# hdmi.net
KiCad netlist of a schematic drawn in EAGLE
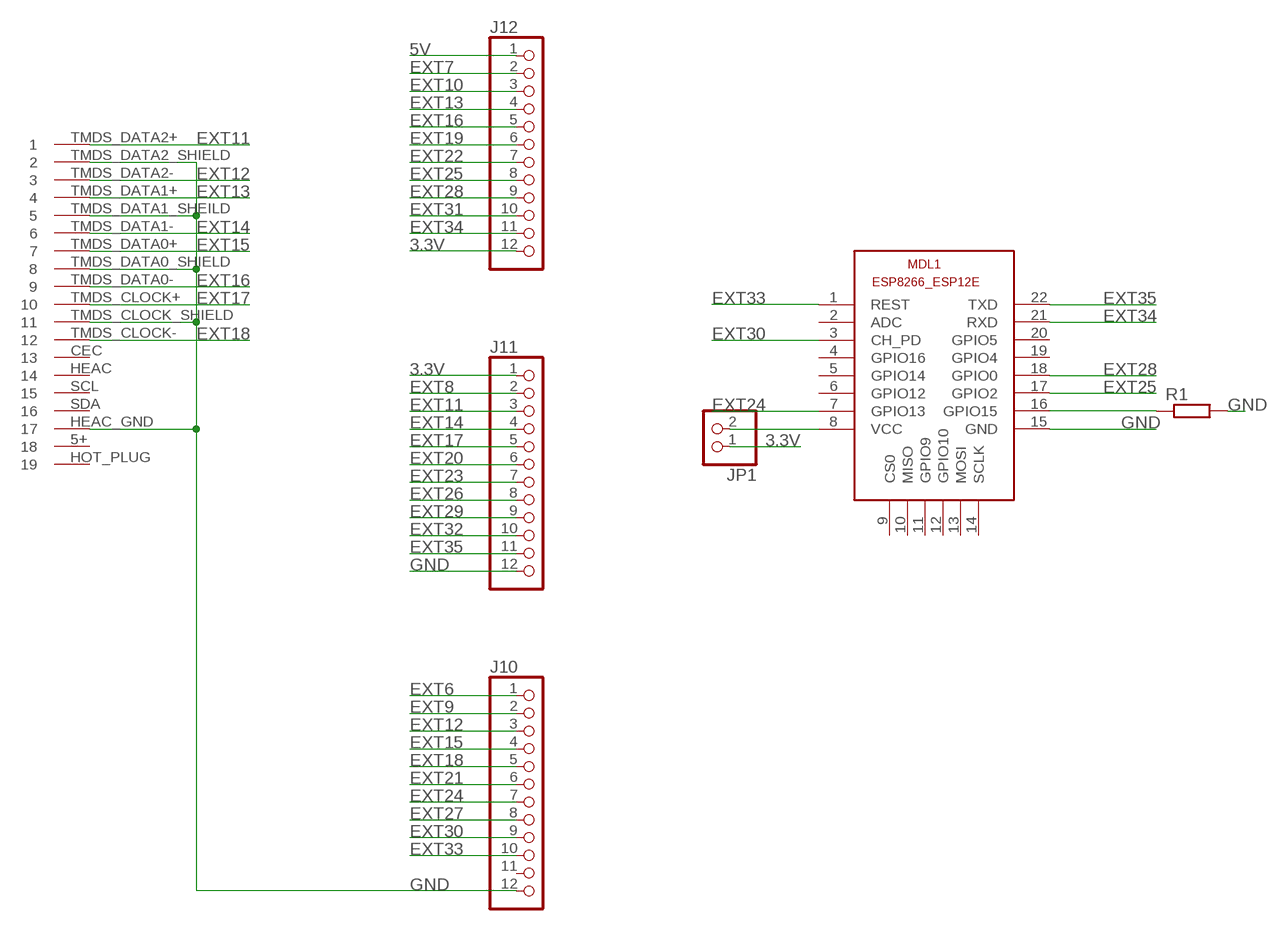
[diagram p0: schematic, sheet 1]

(export (version "E")
  (design (tool "Eeschema 10.0.6"))
  (components
    (comp (ref "J10")
      (value "PINHD-1X12")
      (footprint "eagle-import:1X12")
      (libsource (lib "eagle-import") (part "PINHD-1X12"))
    )
    (comp (ref "J11")
      (value "PINHD-1X12")
      (footprint "eagle-import:1X12")
      (libsource (lib "eagle-import") (part "PINHD-1X12"))
    )
    (comp (ref "J12")
      (value "PINHD-1X12")
      (footprint "eagle-import:1X12")
      (libsource (lib "eagle-import") (part "PINHD-1X12"))
    )
    (comp (ref "JP1")
      (value "PINHD-1X2/90")
      (footprint "eagle-import:1X02_90")
      (libsource (lib "eagle-import") (part "PINHD-1X2/90"))
    )
    (comp (ref "MDL1")
      (value "ESP8266-12EESP8266-ESP12E")
      (footprint "eagle-import:ESP8266-ESP12E")
      (libsource (lib "eagle-import") (part "ESP8266-12EESP8266-ESP12E"))
    )
    (comp (ref "R1")
      (value "R-EU_M0805")
      (footprint "eagle-import:M0805")
      (libsource (lib "eagle-import") (part "R-EU_M0805"))
    )
    (comp (ref "U$2")
      (value "HDMI")
      (footprint "eagle-import:DS1115")
      (libsource (lib "eagle-import") (part "HDMI"))
    )
  )
  (nets
    (net (code "1") (name "/3.3V") (class "Default")
      (node (ref "J11") (pin "1") (pinfunction "1_1") (pintype "passive"))
      (node (ref "J12") (pin "12") (pinfunction "12_12") (pintype "passive"))
      (node (ref "JP1") (pin "1") (pinfunction "1_1") (pintype "passive"))
    )
    (net (code "2") (name "/5V") (class "Default")
      (node (ref "J12") (pin "1") (pinfunction "1_1") (pintype "passive"))
    )
    (net (code "3") (name "/EXT6") (class "Default")
      (node (ref "J10") (pin "1") (pinfunction "1_1") (pintype "passive"))
    )
    (net (code "4") (name "/EXT7") (class "Default")
      (node (ref "J12") (pin "2") (pinfunction "2_2") (pintype "passive"))
    )
    (net (code "5") (name "/EXT8") (class "Default")
      (node (ref "J11") (pin "2") (pinfunction "2_2") (pintype "passive"))
    )
    (net (code "6") (name "/EXT9") (class "Default")
      (node (ref "J10") (pin "2") (pinfunction "2_2") (pintype "passive"))
    )
    (net (code "7") (name "/EXT10") (class "Default")
      (node (ref "J12") (pin "3") (pinfunction "3_3") (pintype "passive"))
    )
    (net (code "8") (name "/EXT11") (class "Default")
      (node (ref "J11") (pin "3") (pinfunction "3_3") (pintype "passive"))
      (node (ref "U$2") (pin "TMDS_DATA2+") (pinfunction "1_TMDS_DATA2+") (pintype "bidirectional"))
    )
    (net (code "9") (name "/EXT12") (class "Default")
      (node (ref "J10") (pin "3") (pinfunction "3_3") (pintype "passive"))
      (node (ref "U$2") (pin "TMDS_DATA2-") (pinfunction "3_TMDS_DATA2-") (pintype "bidirectional"))
    )
    (net (code "10") (name "/EXT13") (class "Default")
      (node (ref "J12") (pin "4") (pinfunction "4_4") (pintype "passive"))
      (node (ref "U$2") (pin "TMDS_DATA1+") (pinfunction "4_TMDS_DATA1+") (pintype "bidirectional"))
    )
    (net (code "11") (name "/EXT14") (class "Default")
      (node (ref "J11") (pin "4") (pinfunction "4_4") (pintype "passive"))
      (node (ref "U$2") (pin "TMDS_DATA1-") (pinfunction "6_TMDS_DATA1-") (pintype "bidirectional"))
    )
    (net (code "12") (name "/EXT15") (class "Default")
      (node (ref "J10") (pin "4") (pinfunction "4_4") (pintype "passive"))
      (node (ref "U$2") (pin "TMDS_DATA0+") (pinfunction "7_TMDS_DATA0+") (pintype "bidirectional"))
    )
    (net (code "13") (name "/EXT16") (class "Default")
      (node (ref "J12") (pin "5") (pinfunction "5_5") (pintype "passive"))
      (node (ref "U$2") (pin "TMDS_DATA0-") (pinfunction "9_TMDS_DATA0-") (pintype "bidirectional"))
    )
    (net (code "14") (name "/EXT17") (class "Default")
      (node (ref "J11") (pin "5") (pinfunction "5_5") (pintype "passive"))
      (node (ref "U$2") (pin "TMDS_CLOCK+") (pinfunction "10_TMDS_CLOCK+") (pintype "bidirectional"))
    )
    (net (code "15") (name "/EXT18") (class "Default")
      (node (ref "J10") (pin "5") (pinfunction "5_5") (pintype "passive"))
      (node (ref "U$2") (pin "TMDS_CLOCK-") (pinfunction "12_TMDS_CLOCK-") (pintype "bidirectional"))
    )
    (net (code "16") (name "/EXT19") (class "Default")
      (node (ref "J12") (pin "6") (pinfunction "6_6") (pintype "passive"))
    )
    (net (code "17") (name "/EXT20") (class "Default")
      (node (ref "J11") (pin "6") (pinfunction "6_6") (pintype "passive"))
    )
    (net (code "18") (name "/EXT21") (class "Default")
      (node (ref "J10") (pin "6") (pinfunction "6_6") (pintype "passive"))
    )
    (net (code "19") (name "/EXT22") (class "Default")
      (node (ref "J12") (pin "7") (pinfunction "7_7") (pintype "passive"))
    )
    (net (code "20") (name "/EXT23") (class "Default")
      (node (ref "J11") (pin "7") (pinfunction "7_7") (pintype "passive"))
    )
    (net (code "21") (name "/EXT24") (class "Default")
      (node (ref "J10") (pin "7") (pinfunction "7_7") (pintype "passive"))
      (node (ref "MDL1") (pin "7") (pinfunction "GPIO13_7") (pintype "bidirectional"))
    )
    (net (code "22") (name "/EXT25") (class "Default")
      (node (ref "J12") (pin "8") (pinfunction "8_8") (pintype "passive"))
      (node (ref "MDL1") (pin "17") (pinfunction "GPIO2_17") (pintype "bidirectional"))
    )
    (net (code "23") (name "/EXT26") (class "Default")
      (node (ref "J11") (pin "8") (pinfunction "8_8") (pintype "passive"))
    )
    (net (code "24") (name "/EXT27") (class "Default")
      (node (ref "J10") (pin "8") (pinfunction "8_8") (pintype "passive"))
    )
    (net (code "25") (name "/EXT28") (class "Default")
      (node (ref "J12") (pin "9") (pinfunction "9_9") (pintype "passive"))
      (node (ref "MDL1") (pin "18") (pinfunction "GPIO0_18") (pintype "bidirectional"))
    )
    (net (code "26") (name "/EXT29") (class "Default")
      (node (ref "J11") (pin "9") (pinfunction "9_9") (pintype "passive"))
    )
    (net (code "27") (name "/EXT30") (class "Default")
      (node (ref "J10") (pin "9") (pinfunction "9_9") (pintype "passive"))
      (node (ref "MDL1") (pin "3") (pinfunction "CH_PD_3") (pintype "bidirectional"))
    )
    (net (code "28") (name "/EXT31") (class "Default")
      (node (ref "J12") (pin "10") (pinfunction "10_10") (pintype "passive"))
    )
    (net (code "29") (name "/EXT32") (class "Default")
      (node (ref "J11") (pin "10") (pinfunction "10_10") (pintype "passive"))
    )
    (net (code "30") (name "/EXT33") (class "Default")
      (node (ref "J10") (pin "10") (pinfunction "10_10") (pintype "passive"))
      (node (ref "MDL1") (pin "1") (pinfunction "REST_1") (pintype "bidirectional"))
    )
    (net (code "31") (name "/EXT34") (class "Default")
      (node (ref "J12") (pin "11") (pinfunction "11_11") (pintype "passive"))
      (node (ref "MDL1") (pin "21") (pinfunction "RXD_21") (pintype "bidirectional"))
    )
    (net (code "32") (name "/EXT35") (class "Default")
      (node (ref "J11") (pin "11") (pinfunction "11_11") (pintype "passive"))
      (node (ref "MDL1") (pin "22") (pinfunction "TXD_22") (pintype "bidirectional"))
    )
    (net (code "33") (name "/GND") (class "Default")
      (node (ref "J10") (pin "12") (pinfunction "12_12") (pintype "passive"))
      (node (ref "J11") (pin "12") (pinfunction "12_12") (pintype "passive"))
      (node (ref "MDL1") (pin "15") (pinfunction "GND_15") (pintype "bidirectional"))
      (node (ref "R1") (pin "2") (pinfunction "2_2") (pintype "passive"))
      (node (ref "U$2") (pin "HEAC_GND") (pinfunction "17_HEAC_GND") (pintype "bidirectional"))
      (node (ref "U$2") (pin "TMDS_CLOCK_SHIELD") (pinfunction "11_TMDS_CLOCK_SHIELD") (pintype "bidirectional"))
      (node (ref "U$2") (pin "TMDS_DATA0_SHIELD") (pinfunction "8_TMDS_DATA0_SHIELD") (pintype "bidirectional"))
      (node (ref "U$2") (pin "TMDS_DATA1_SHEILD") (pinfunction "5_TMDS_DATA1_SHEILD") (pintype "bidirectional"))
      (node (ref "U$2") (pin "TMDS_DATA2_SHIELD") (pinfunction "2_TMDS_DATA2_SHIELD") (pintype "bidirectional"))
    )
    (net (code "34") (name "Net-(MDL1-GPIO15)") (class "Default")
      (node (ref "MDL1") (pin "16") (pinfunction "GPIO15_16") (pintype "bidirectional"))
      (node (ref "R1") (pin "1") (pinfunction "1_1") (pintype "passive"))
    )
    (net (code "35") (name "Net-(MDL1-VCC)") (class "Default")
      (node (ref "JP1") (pin "2") (pinfunction "2_2") (pintype "passive"))
      (node (ref "MDL1") (pin "8") (pinfunction "VCC_8") (pintype "bidirectional"))
    )
    (net (code "36") (name "unconnected-(J10-Pad11)") (class "Default")
      (node (ref "J10") (pin "11") (pinfunction "11_11") (pintype "passive"))
    )
    (net (code "37") (name "unconnected-(MDL1-ADC-Pad2)") (class "Default")
      (node (ref "MDL1") (pin "2") (pinfunction "ADC_2") (pintype "bidirectional"))
    )
    (net (code "38") (name "unconnected-(MDL1-CS0-Pad9)") (class "Default")
      (node (ref "MDL1") (pin "9") (pinfunction "CS0_9") (pintype "bidirectional"))
    )
    (net (code "39") (name "unconnected-(MDL1-GPIO4-Pad19)") (class "Default")
      (node (ref "MDL1") (pin "19") (pinfunction "GPIO4_19") (pintype "bidirectional"))
    )
    (net (code "40") (name "unconnected-(MDL1-GPIO5-Pad20)") (class "Default")
      (node (ref "MDL1") (pin "20") (pinfunction "GPIO5_20") (pintype "bidirectional"))
    )
    (net (code "41") (name "unconnected-(MDL1-GPIO9-Pad11)") (class "Default")
      (node (ref "MDL1") (pin "11") (pinfunction "GPIO9_11") (pintype "bidirectional"))
    )
    (net (code "42") (name "unconnected-(MDL1-GPIO10-Pad12)") (class "Default")
      (node (ref "MDL1") (pin "12") (pinfunction "GPIO10_12") (pintype "bidirectional"))
    )
    (net (code "43") (name "unconnected-(MDL1-GPIO12-Pad6)") (class "Default")
      (node (ref "MDL1") (pin "6") (pinfunction "GPIO12_6") (pintype "bidirectional"))
    )
    (net (code "44") (name "unconnected-(MDL1-GPIO14-Pad5)") (class "Default")
      (node (ref "MDL1") (pin "5") (pinfunction "GPIO14_5") (pintype "bidirectional"))
    )
    (net (code "45") (name "unconnected-(MDL1-GPIO16-Pad4)") (class "Default")
      (node (ref "MDL1") (pin "4") (pinfunction "GPIO16_4") (pintype "bidirectional"))
    )
    (net (code "46") (name "unconnected-(MDL1-MISO-Pad10)") (class "Default")
      (node (ref "MDL1") (pin "10") (pinfunction "MISO_10") (pintype "bidirectional"))
    )
    (net (code "47") (name "unconnected-(MDL1-MOSI-Pad13)") (class "Default")
      (node (ref "MDL1") (pin "13") (pinfunction "MOSI_13") (pintype "bidirectional"))
    )
    (net (code "48") (name "unconnected-(MDL1-SCLK-Pad14)") (class "Default")
      (node (ref "MDL1") (pin "14") (pinfunction "SCLK_14") (pintype "bidirectional"))
    )
    (net (code "49") (name "unconnected-(U$2-13-PadCEC)") (class "Default")
      (node (ref "U$2") (pin "CEC") (pinfunction "13_CEC") (pintype "bidirectional"))
    )
    (net (code "50") (name "unconnected-(U$2-14-PadHEAC)") (class "Default")
      (node (ref "U$2") (pin "HEAC") (pinfunction "14_HEAC") (pintype "bidirectional"))
    )
    (net (code "51") (name "unconnected-(U$2-15-PadSCL)") (class "Default")
      (node (ref "U$2") (pin "SCL") (pinfunction "15_SCL") (pintype "bidirectional"))
    )
    (net (code "52") (name "unconnected-(U$2-16-PadSDA)") (class "Default")
      (node (ref "U$2") (pin "SDA") (pinfunction "16_SDA") (pintype "bidirectional"))
    )
    (net (code "53") (name "unconnected-(U$2-18-Pad5+)") (class "Default")
      (node (ref "U$2") (pin "5+") (pinfunction "18_5+") (pintype "bidirectional"))
    )
    (net (code "54") (name "unconnected-(U$2-19-PadHOT_PLUG)") (class "Default")
      (node (ref "U$2") (pin "HOT_PLUG") (pinfunction "19_HOT_PLUG") (pintype "bidirectional"))
    )
  )
)
